# acs758.net
KiCad netlist of a schematic drawn in EAGLE
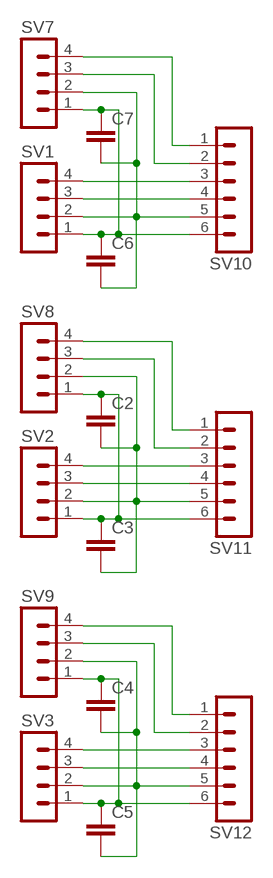
[diagram p0: schematic, sheet 1]

(export (version "E")
  (design (tool "Eeschema 10.0.6"))
  (components
    (comp (ref "C2")
      (value "C-EU025-025X050")
      (footprint "eagle-import:C025-025X050")
      (libsource (lib "eagle-import") (part "C-EU025-025X050"))
    )
    (comp (ref "C3")
      (value "C-EU025-025X050")
      (footprint "eagle-import:C025-025X050")
      (libsource (lib "eagle-import") (part "C-EU025-025X050"))
    )
    (comp (ref "C4")
      (value "C-EU025-025X050")
      (footprint "eagle-import:C025-025X050")
      (libsource (lib "eagle-import") (part "C-EU025-025X050"))
    )
    (comp (ref "C5")
      (value "C-EU025-025X050")
      (footprint "eagle-import:C025-025X050")
      (libsource (lib "eagle-import") (part "C-EU025-025X050"))
    )
    (comp (ref "C6")
      (value "C-EU025-025X050")
      (footprint "eagle-import:C025-025X050")
      (libsource (lib "eagle-import") (part "C-EU025-025X050"))
    )
    (comp (ref "C7")
      (value "C-EU025-025X050")
      (footprint "eagle-import:C025-025X050")
      (libsource (lib "eagle-import") (part "C-EU025-025X050"))
    )
    (comp (ref "SV1")
      (value "MA04-1")
      (footprint "eagle-import:MA04-1")
      (libsource (lib "eagle-import") (part "MA04-1"))
    )
    (comp (ref "SV2")
      (value "MA04-1")
      (footprint "eagle-import:MA04-1")
      (libsource (lib "eagle-import") (part "MA04-1"))
    )
    (comp (ref "SV3")
      (value "MA04-1")
      (footprint "eagle-import:MA04-1")
      (libsource (lib "eagle-import") (part "MA04-1"))
    )
    (comp (ref "SV7")
      (value "MA04-1")
      (footprint "eagle-import:MA04-1")
      (libsource (lib "eagle-import") (part "MA04-1"))
    )
    (comp (ref "SV8")
      (value "MA04-1")
      (footprint "eagle-import:MA04-1")
      (libsource (lib "eagle-import") (part "MA04-1"))
    )
    (comp (ref "SV9")
      (value "MA04-1")
      (footprint "eagle-import:MA04-1")
      (libsource (lib "eagle-import") (part "MA04-1"))
    )
    (comp (ref "SV10")
      (value "MA06-1")
      (footprint "eagle-import:MA06-1")
      (libsource (lib "eagle-import") (part "MA06-1"))
    )
    (comp (ref "SV11")
      (value "MA06-1")
      (footprint "eagle-import:MA06-1")
      (libsource (lib "eagle-import") (part "MA06-1"))
    )
    (comp (ref "SV12")
      (value "MA06-1")
      (footprint "eagle-import:MA06-1")
      (libsource (lib "eagle-import") (part "MA06-1"))
    )
  )
  (nets
    (net (code "1") (name "Net-(C2-Pad1)") (class "Default")
      (node (ref "C2") (pin "1") (pinfunction "1_1") (pintype "passive"))
      (node (ref "C3") (pin "1") (pinfunction "1_1") (pintype "passive"))
      (node (ref "SV11") (pin "6") (pinfunction "6_6") (pintype "passive"))
      (node (ref "SV2") (pin "1") (pinfunction "1_1") (pintype "passive"))
      (node (ref "SV8") (pin "1") (pinfunction "1_1") (pintype "passive"))
    )
    (net (code "2") (name "Net-(C2-Pad2)") (class "Default")
      (node (ref "C2") (pin "2") (pinfunction "2_2") (pintype "passive"))
      (node (ref "C3") (pin "2") (pinfunction "2_2") (pintype "passive"))
      (node (ref "SV11") (pin "5") (pinfunction "5_5") (pintype "passive"))
      (node (ref "SV2") (pin "2") (pinfunction "2_2") (pintype "passive"))
      (node (ref "SV8") (pin "2") (pinfunction "2_2") (pintype "passive"))
    )
    (net (code "3") (name "Net-(C4-Pad1)") (class "Default")
      (node (ref "C4") (pin "1") (pinfunction "1_1") (pintype "passive"))
      (node (ref "C5") (pin "1") (pinfunction "1_1") (pintype "passive"))
      (node (ref "SV12") (pin "6") (pinfunction "6_6") (pintype "passive"))
      (node (ref "SV3") (pin "1") (pinfunction "1_1") (pintype "passive"))
      (node (ref "SV9") (pin "1") (pinfunction "1_1") (pintype "passive"))
    )
    (net (code "4") (name "Net-(C4-Pad2)") (class "Default")
      (node (ref "C4") (pin "2") (pinfunction "2_2") (pintype "passive"))
      (node (ref "C5") (pin "2") (pinfunction "2_2") (pintype "passive"))
      (node (ref "SV12") (pin "5") (pinfunction "5_5") (pintype "passive"))
      (node (ref "SV3") (pin "2") (pinfunction "2_2") (pintype "passive"))
      (node (ref "SV9") (pin "2") (pinfunction "2_2") (pintype "passive"))
    )
    (net (code "5") (name "Net-(C6-Pad1)") (class "Default")
      (node (ref "C6") (pin "1") (pinfunction "1_1") (pintype "passive"))
      (node (ref "C7") (pin "1") (pinfunction "1_1") (pintype "passive"))
      (node (ref "SV1") (pin "1") (pinfunction "1_1") (pintype "passive"))
      (node (ref "SV10") (pin "6") (pinfunction "6_6") (pintype "passive"))
      (node (ref "SV7") (pin "1") (pinfunction "1_1") (pintype "passive"))
    )
    (net (code "6") (name "Net-(C6-Pad2)") (class "Default")
      (node (ref "C6") (pin "2") (pinfunction "2_2") (pintype "passive"))
      (node (ref "C7") (pin "2") (pinfunction "2_2") (pintype "passive"))
      (node (ref "SV1") (pin "2") (pinfunction "2_2") (pintype "passive"))
      (node (ref "SV10") (pin "5") (pinfunction "5_5") (pintype "passive"))
      (node (ref "SV7") (pin "2") (pinfunction "2_2") (pintype "passive"))
    )
    (net (code "7") (name "Net-(SV1-Pad3)") (class "Default")
      (node (ref "SV1") (pin "3") (pinfunction "3_3") (pintype "passive"))
      (node (ref "SV10") (pin "4") (pinfunction "4_4") (pintype "passive"))
    )
    (net (code "8") (name "Net-(SV1-Pad4)") (class "Default")
      (node (ref "SV1") (pin "4") (pinfunction "4_4") (pintype "passive"))
      (node (ref "SV10") (pin "3") (pinfunction "3_3") (pintype "passive"))
    )
    (net (code "9") (name "Net-(SV10-Pad1)") (class "Default")
      (node (ref "SV10") (pin "1") (pinfunction "1_1") (pintype "passive"))
      (node (ref "SV7") (pin "4") (pinfunction "4_4") (pintype "passive"))
    )
    (net (code "10") (name "Net-(SV10-Pad2)") (class "Default")
      (node (ref "SV10") (pin "2") (pinfunction "2_2") (pintype "passive"))
      (node (ref "SV7") (pin "3") (pinfunction "3_3") (pintype "passive"))
    )
    (net (code "11") (name "Net-(SV11-Pad1)") (class "Default")
      (node (ref "SV11") (pin "1") (pinfunction "1_1") (pintype "passive"))
      (node (ref "SV8") (pin "4") (pinfunction "4_4") (pintype "passive"))
    )
    (net (code "12") (name "Net-(SV11-Pad2)") (class "Default")
      (node (ref "SV11") (pin "2") (pinfunction "2_2") (pintype "passive"))
      (node (ref "SV8") (pin "3") (pinfunction "3_3") (pintype "passive"))
    )
    (net (code "13") (name "Net-(SV11-Pad3)") (class "Default")
      (node (ref "SV11") (pin "3") (pinfunction "3_3") (pintype "passive"))
      (node (ref "SV2") (pin "4") (pinfunction "4_4") (pintype "passive"))
    )
    (net (code "14") (name "Net-(SV11-Pad4)") (class "Default")
      (node (ref "SV11") (pin "4") (pinfunction "4_4") (pintype "passive"))
      (node (ref "SV2") (pin "3") (pinfunction "3_3") (pintype "passive"))
    )
    (net (code "15") (name "Net-(SV12-Pad1)") (class "Default")
      (node (ref "SV12") (pin "1") (pinfunction "1_1") (pintype "passive"))
      (node (ref "SV9") (pin "4") (pinfunction "4_4") (pintype "passive"))
    )
    (net (code "16") (name "Net-(SV12-Pad2)") (class "Default")
      (node (ref "SV12") (pin "2") (pinfunction "2_2") (pintype "passive"))
      (node (ref "SV9") (pin "3") (pinfunction "3_3") (pintype "passive"))
    )
    (net (code "17") (name "Net-(SV12-Pad3)") (class "Default")
      (node (ref "SV12") (pin "3") (pinfunction "3_3") (pintype "passive"))
      (node (ref "SV3") (pin "4") (pinfunction "4_4") (pintype "passive"))
    )
    (net (code "18") (name "Net-(SV12-Pad4)") (class "Default")
      (node (ref "SV12") (pin "4") (pinfunction "4_4") (pintype "passive"))
      (node (ref "SV3") (pin "3") (pinfunction "3_3") (pintype "passive"))
    )
  )
)
